# Measurement.net
KiCad netlist of a schematic drawn in Altium Designer
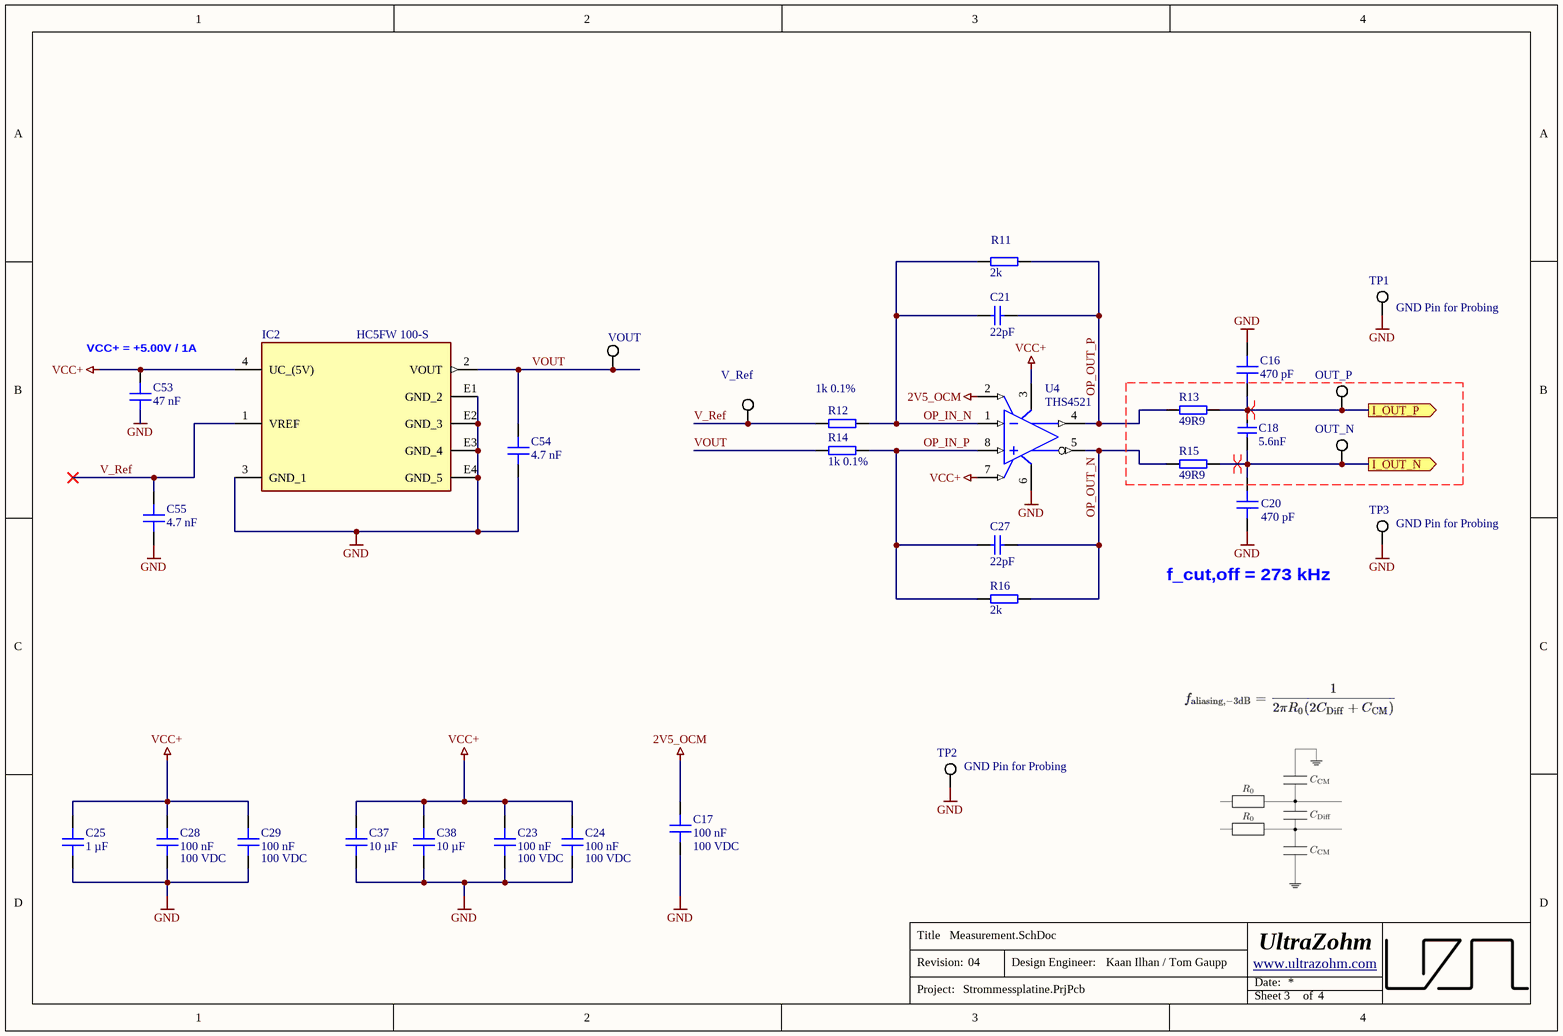
[diagram p0: Measurement.SchDoc]

(export (version "E")
  (design (tool "Eeschema 10.0.6"))
  (components
    (comp (ref "C16")
      (value "470 pF")
      (footprint "C_0603")
      (description "50V 470pF X7R ±10% 0603 Multilayer Ceramic Capacitors MLCC - SMD/SMT ROHS")
      (fields
        (field (name "MANUFACTURER PART NUMBER") "C0603C471K5RACAUTO")
        (field (name "MANUFACTURER") "KEMET")
        (field (name "CREATED FROM") "KIlhan")
      )
      (libsource (lib "user") (part "Capacitor"))
    )
    (comp (ref "C17")
      (value "100 nF")
      (footprint "C_0603")
      (description "100V 100nF X7S ±10% 0603 Multilayer Ceramic Capacitors MLCC - SMD/SMT ROHS")
      (fields
        (field (name "MANUFACTURER PART NUMBER") "C1608X7S2A104KT000N")
        (field (name "MANUFACTURER") "TDK")
        (field (name "VOLTAGE RATING") "100 VDC")
        (field (name "CREATED FROM") "AGeiger")
      )
      (libsource (lib "user") (part "Capacitor"))
    )
    (comp (ref "C18")
      (value "5.6nF")
      (footprint "C_0603_TE")
      (description "50V 5.6nF X7R ±10% 0603 Multilayer Ceramic Capacitors MLCC - SMD/SMT ROHS")
      (fields
        (field (name "MANUFACTURER PART NUMBER") "0603B562K500NT")
        (field (name "MANUFACTURER") "FH (Guangdong Fenghua Advanced Tech)")
        (field (name "CREATED FROM") "Kilhan")
      )
      (libsource (lib "user") (part "CAP-NP"))
    )
    (comp (ref "C20")
      (value "470 pF")
      (footprint "C_0603")
      (description "50V 470pF X7R ±10% 0603 Multilayer Ceramic Capacitors MLCC - SMD/SMT ROHS")
      (fields
        (field (name "MANUFACTURER PART NUMBER") "C0603C471K5RACAUTO")
        (field (name "MANUFACTURER") "KEMET")
        (field (name "CREATED FROM") "KIlhan")
      )
      (libsource (lib "user") (part "Capacitor"))
    )
    (comp (ref "C21")
      (value "22pF")
      (footprint "C_0603_TE")
      (description "50V 22pF C0G ±5% 0603 Multilayer Ceramic Capacitors MLCC - SMD/SMT ROHS")
      (fields
        (field (name "MANUFACTURER PART NUMBER") "CL10C220JB8NNNC")
        (field (name "MANUFACTURER") "Samsung Electro-Mechanics")
        (field (name "CREATED FROM") "Kilhan")
      )
      (libsource (lib "user") (part "CAP-NP"))
    )
    (comp (ref "C23")
      (value "100 nF")
      (footprint "C_0603")
      (description "100V 100nF X7S ±10% 0603 Multilayer Ceramic Capacitors MLCC - SMD/SMT ROHS")
      (fields
        (field (name "MANUFACTURER PART NUMBER") "C1608X7S2A104KT000N")
        (field (name "MANUFACTURER") "TDK")
        (field (name "VOLTAGE RATING") "100 VDC")
        (field (name "CREATED FROM") "AGeiger")
      )
      (libsource (lib "user") (part "Capacitor"))
    )
    (comp (ref "C24")
      (value "100 nF")
      (footprint "C_0603")
      (description "100V 100nF X7S ±10% 0603 Multilayer Ceramic Capacitors MLCC - SMD/SMT ROHS")
      (fields
        (field (name "MANUFACTURER PART NUMBER") "C1608X7S2A104KT000N")
        (field (name "MANUFACTURER") "TDK")
        (field (name "VOLTAGE RATING") "100 VDC")
        (field (name "CREATED FROM") "AGeiger")
      )
      (libsource (lib "user") (part "Capacitor"))
    )
    (comp (ref "C25")
      (value "1 µF")
      (footprint "C_0603")
      (description "50V 1uF X5R ±10% 0603  Multilayer Ceramic Capacitors MLCC - SMD/SMT ROHS")
      (fields
        (field (name "MANUFACTURER PART NUMBER") "CL10A105KB8NNNC")
        (field (name "MANUFACTURER") "Samsung Electro-Mechanics")
        (field (name "CREATED FROM") "MGremer")
      )
      (libsource (lib "user") (part "Capacitor"))
    )
    (comp (ref "C27")
      (value "22pF")
      (footprint "C_0603_TE")
      (description "50V 22pF C0G ±5% 0603 Multilayer Ceramic Capacitors MLCC - SMD/SMT ROHS")
      (fields
        (field (name "MANUFACTURER PART NUMBER") "CL10C220JB8NNNC")
        (field (name "MANUFACTURER") "Samsung Electro-Mechanics")
        (field (name "CREATED FROM") "Kilhan")
      )
      (libsource (lib "user") (part "CAP-NP"))
    )
    (comp (ref "C28")
      (value "100 nF")
      (footprint "C_0603")
      (description "100V 100nF X7S ±10% 0603 Multilayer Ceramic Capacitors MLCC - SMD/SMT ROHS")
      (fields
        (field (name "MANUFACTURER PART NUMBER") "C1608X7S2A104KT000N")
        (field (name "MANUFACTURER") "TDK")
        (field (name "VOLTAGE RATING") "100 VDC")
        (field (name "CREATED FROM") "AGeiger")
      )
      (libsource (lib "user") (part "Capacitor"))
    )
    (comp (ref "C29")
      (value "100 nF")
      (footprint "C_0603")
      (description "100V 100nF X7S ±10% 0603 Multilayer Ceramic Capacitors MLCC - SMD/SMT ROHS")
      (fields
        (field (name "MANUFACTURER PART NUMBER") "C1608X7S2A104KT000N")
        (field (name "MANUFACTURER") "TDK")
        (field (name "VOLTAGE RATING") "100 VDC")
        (field (name "CREATED FROM") "AGeiger")
      )
      (libsource (lib "user") (part "Capacitor"))
    )
    (comp (ref "C37")
      (value "10 µF")
      (footprint "C0805")
      (description "Capacitor 0805, 35 VDC, 10 µF, X5R")
      (fields
        (field (name "MANUFACTURER PART NUMBER") "GRM21BR6YA106KE43L")
        (field (name "MANUFACTURER") "muRata")
        (field (name "CREATED FROM") "MGremer")
      )
      (libsource (lib "user") (part "Capacitor"))
    )
    (comp (ref "C38")
      (value "10 µF")
      (footprint "C0805")
      (description "Capacitor 0805, 35 VDC, 10 µF, X5R")
      (fields
        (field (name "MANUFACTURER PART NUMBER") "GRM21BR6YA106KE43L")
        (field (name "MANUFACTURER") "muRata")
        (field (name "CREATED FROM") "MGremer")
      )
      (libsource (lib "user") (part "Capacitor"))
    )
    (comp (ref "C53")
      (value "47 nF")
      (footprint "C_0603")
      (description "Capacitor 0603, 50 VDC, 47 nF, X7R")
      (fields
        (field (name "MANUFACTURER PART NUMBER") "CL10B473KB8NNNC")
        (field (name "MANUFACTURER") "Samsung Electro-Mechanics")
        (field (name "CREATED FROM") "DHufnagel")
      )
      (libsource (lib "user") (part "Capacitor"))
    )
    (comp (ref "C54")
      (value "4.7 nF")
      (footprint "C_0603")
      (description "Capacitor 0603, 16 VDC, 4.7 nF, X7R")
      (fields
        (field (name "MANUFACTURER PART NUMBER") "C0603C472K4RECAUTO")
        (field (name "MANUFACTURER") "KEMET")
        (field (name "CREATED FROM") "MGremer")
      )
      (libsource (lib "user") (part "Capacitor"))
    )
    (comp (ref "C55")
      (value "4.7 nF")
      (footprint "C_0603")
      (description "Capacitor 0603, 16 VDC, 4.7 nF, X7R")
      (fields
        (field (name "MANUFACTURER PART NUMBER") "C0603C472K4RECAUTO")
        (field (name "MANUFACTURER") "KEMET")
        (field (name "CREATED FROM") "MGremer")
      )
      (libsource (lib "user") (part "Capacitor"))
    )
    (comp (ref "IC2")
      (value "HC5FW 100-S")
      (footprint "LEM_HC5FW")
      (description "-100 A - 100 A, 40 kHz")
      (fields (field (name "MANUFACTURER") "LEM") (field (name "CREATED FROM") "TGaupp"))
      (libsource (lib "user") (part "LEM_HC5FW"))
    )
    (comp (ref "OUT_N")
      (value "5015")
      (footprint "KSTN-5019_V")
      (description "Circuit Board Hardware - PCB SM TEST POINT ON T&R - MINIATURE")
      (fields
        (field (name "MANUFACTURER") "Keystone Electronics")
        (field (name "LCSC PART NUMBER") "C5199798")
        (field (name "CREATED FROM") "AGeiger")
      )
      (libsource (lib "user") (part "SMD Testpoint"))
    )
    (comp (ref "OUT_P")
      (value "5015")
      (footprint "KSTN-5019_V")
      (description "Circuit Board Hardware - PCB SM TEST POINT ON T&R - MINIATURE")
      (fields
        (field (name "MANUFACTURER") "Keystone Electronics")
        (field (name "LCSC PART NUMBER") "C5199798")
        (field (name "CREATED FROM") "AGeiger")
      )
      (libsource (lib "user") (part "SMD Testpoint"))
    )
    (comp (ref "R11")
      (value "2k")
      (footprint "RES 0603_1608")
      (description "SMD resistor 0.1%")
      (fields
        (field (name "MANUFACTURER PART NUMBER") "ERJ-PB3B2001V")
        (field (name "MANUFACTURER") "Panasonic")
        (field (name "CREATED FROM") "DHufnagel")
      )
      (libsource (lib "user") (part "Resistor"))
    )
    (comp (ref "R12")
      (value "1k 0.1%")
      (footprint "RES 0603_1608")
      (description "100mW ±0.1% ±25ppm/℃ 1kΩ 0603 Chip Resistor - Surface Mount ROHS")
      (fields
        (field (name "MANUFACTURER PART NUMBER") "AR03BTCX1001")
        (field (name "MANUFACTURER") "Viking Tech")
        (field (name "CREATED FROM") "AGeiger")
      )
      (libsource (lib "user") (part "Resistor"))
    )
    (comp (ref "R13")
      (value "49R9")
      (footprint "RES 0603_1608")
      (description "100mW Thick Film Resistors ±100ppm/℃ ±1% 49.9Ω 0603 Chip Resistor - Surface Mount ROHS")
      (fields
        (field (name "MANUFACTURER PART NUMBER") "RC0603FR-0749R9L")
        (field (name "MANUFACTURER") "YAGEO")
        (field (name "CREATED FROM") "AGeiger")
      )
      (libsource (lib "user") (part "Resistor"))
    )
    (comp (ref "R14")
      (value "1k 0.1%")
      (footprint "RES 0603_1608")
      (description "100mW ±0.1% ±25ppm/℃ 1kΩ 0603 Chip Resistor - Surface Mount ROHS")
      (fields
        (field (name "MANUFACTURER PART NUMBER") "AR03BTCX1001")
        (field (name "MANUFACTURER") "Viking Tech")
        (field (name "CREATED FROM") "AGeiger")
      )
      (libsource (lib "user") (part "Resistor"))
    )
    (comp (ref "R15")
      (value "49R9")
      (footprint "RES 0603_1608")
      (description "100mW Thick Film Resistors ±100ppm/℃ ±1% 49.9Ω 0603 Chip Resistor - Surface Mount ROHS")
      (fields
        (field (name "MANUFACTURER PART NUMBER") "RC0603FR-0749R9L")
        (field (name "MANUFACTURER") "YAGEO")
        (field (name "CREATED FROM") "AGeiger")
      )
      (libsource (lib "user") (part "Resistor"))
    )
    (comp (ref "R16")
      (value "2k")
      (footprint "RES 0603_1608")
      (description "SMD resistor 0.1%")
      (fields
        (field (name "MANUFACTURER PART NUMBER") "ERJ-PB3B2001V")
        (field (name "MANUFACTURER") "Panasonic")
        (field (name "CREATED FROM") "DHufnagel")
      )
      (libsource (lib "user") (part "Resistor"))
    )
    (comp (ref "TP1")
      (value "5015")
      (footprint "KSTN-5019_V")
      (description "Circuit Board Hardware - PCB SM TEST POINT ON T&R - MINIATURE")
      (fields
        (field (name "MANUFACTURER") "Keystone Electronics")
        (field (name "LCSC PART NUMBER") "C5199798")
        (field (name "CREATED FROM") "AGeiger")
      )
      (libsource (lib "user") (part "SMD Testpoint"))
    )
    (comp (ref "TP2")
      (value "5015")
      (footprint "KSTN-5019_V")
      (description "Circuit Board Hardware - PCB SM TEST POINT ON T&R - MINIATURE")
      (fields
        (field (name "MANUFACTURER") "Keystone Electronics")
        (field (name "LCSC PART NUMBER") "C5199798")
        (field (name "CREATED FROM") "AGeiger")
      )
      (libsource (lib "user") (part "SMD Testpoint"))
    )
    (comp (ref "TP3")
      (value "5015")
      (footprint "KSTN-5019_V")
      (description "Circuit Board Hardware - PCB SM TEST POINT ON T&R - MINIATURE")
      (fields
        (field (name "MANUFACTURER") "Keystone Electronics")
        (field (name "LCSC PART NUMBER") "C5199798")
        (field (name "CREATED FROM") "AGeiger")
      )
      (libsource (lib "user") (part "SMD Testpoint"))
    )
    (comp (ref "U4")
      (value "THS4521")
      (footprint "ADA4940-1ARZ-R7")
      (description "145MHz 240uV 700nA Single Channel 95MHz SOIC-8 Differential Amplifiers ROHS")
      (fields
        (field (name "MANUFACTURER") "Texas Instruments")
        (field (name "MANUFACTURER PART NUMBER") "THS4521IDR")
      )
      (libsource (lib "UltraZohm_ADC") (part "THS4521IDGKR"))
    )
    (comp (ref "VOUT")
      (value "5019")
      (footprint "KSTN-5019_V")
      (description "Circuit Board Hardware - PCB SM TEST POINT ON T&R - MINIATURE")
      (fields
        (field (name "MANUFACTURER") "Keystone Electronics")
        (field (name "LCSC PART NUMBER") "C5199800")
        (field (name "CREATED FROM") "AGeiger")
      )
      (libsource (lib "user") (part "SMD Testpoint"))
    )
    (comp (ref "V_Ref")
      (value "5015")
      (footprint "KSTN-5019_V")
      (description "Circuit Board Hardware - PCB SM TEST POINT ON T&R - MINIATURE")
      (fields
        (field (name "MANUFACTURER") "Keystone Electronics")
        (field (name "LCSC PART NUMBER") "C5199798")
        (field (name "CREATED FROM") "AGeiger")
      )
      (libsource (lib "user") (part "SMD Testpoint"))
    )
  )
  (nets
    (net (code "1") (name "/I_OUT_N") (class "Default")
      (node (ref "C18") (pin "2") (pinfunction "2_2") (pintype "passive"))
      (node (ref "C20") (pin "1") (pinfunction "1_1") (pintype "passive"))
      (node (ref "OUT_N") (pin "1") (pinfunction "1_1") (pintype "passive"))
      (node (ref "R15") (pin "2") (pinfunction "2_2") (pintype "passive"))
    )
    (net (code "2") (name "/I_OUT_P") (class "Default")
      (node (ref "C16") (pin "2") (pinfunction "2_2") (pintype "passive"))
      (node (ref "C18") (pin "1") (pinfunction "1_1") (pintype "passive"))
      (node (ref "OUT_P") (pin "1") (pinfunction "1_1") (pintype "passive"))
      (node (ref "R13") (pin "2") (pinfunction "2_2") (pintype "passive"))
    )
    (net (code "3") (name "/OP_IN_N") (class "Default")
      (node (ref "C21") (pin "2") (pinfunction "2_2") (pintype "passive"))
      (node (ref "R11") (pin "1") (pinfunction "1_1") (pintype "passive"))
      (node (ref "R12") (pin "2") (pinfunction "2_2") (pintype "passive"))
      (node (ref "U4") (pin "1") (pinfunction "VIN-_1") (pintype "input"))
    )
    (net (code "4") (name "/OP_IN_P") (class "Default")
      (node (ref "C27") (pin "2") (pinfunction "2_2") (pintype "passive"))
      (node (ref "R14") (pin "2") (pinfunction "2_2") (pintype "passive"))
      (node (ref "R16") (pin "1") (pinfunction "1_1") (pintype "passive"))
      (node (ref "U4") (pin "8") (pinfunction "VIN+_8") (pintype "input"))
    )
    (net (code "5") (name "/OP_OUT_N") (class "Default")
      (node (ref "C27") (pin "1") (pinfunction "1_1") (pintype "passive"))
      (node (ref "R15") (pin "1") (pinfunction "1_1") (pintype "passive"))
      (node (ref "R16") (pin "2") (pinfunction "2_2") (pintype "passive"))
      (node (ref "U4") (pin "5") (pinfunction "VOUT-_5") (pintype "output"))
    )
    (net (code "6") (name "/OP_OUT_P") (class "Default")
      (node (ref "C21") (pin "1") (pinfunction "1_1") (pintype "passive"))
      (node (ref "R11") (pin "2") (pinfunction "2_2") (pintype "passive"))
      (node (ref "R13") (pin "1") (pinfunction "1_1") (pintype "passive"))
      (node (ref "U4") (pin "4") (pinfunction "VOUT+_4") (pintype "output"))
    )
    (net (code "7") (name "/VOUT") (class "Default")
      (node (ref "C54") (pin "2") (pinfunction "2_2") (pintype "passive"))
      (node (ref "IC2") (pin "2") (pinfunction "VOUT_2") (pintype "output"))
      (node (ref "R14") (pin "1") (pinfunction "1_1") (pintype "passive"))
      (node (ref "VOUT") (pin "1") (pinfunction "1_1") (pintype "passive"))
    )
    (net (code "8") (name "/V_Ref") (class "Default")
      (node (ref "C55") (pin "2") (pinfunction "2_2") (pintype "passive"))
      (node (ref "IC2") (pin "1") (pinfunction "VREF_1") (pintype "passive"))
      (node (ref "R12") (pin "1") (pinfunction "1_1") (pintype "passive"))
      (node (ref "V_Ref") (pin "1") (pinfunction "1_1") (pintype "passive"))
    )
    (net (code "9") (name "2V5_OCM") (class "Default")
      (node (ref "C17") (pin "1") (pinfunction "1_1") (pintype "passive"))
      (node (ref "U4") (pin "2") (pinfunction "VOCM_2") (pintype "input"))
    )
    (net (code "10") (name "GND") (class "Default")
      (node (ref "C16") (pin "1") (pinfunction "1_1") (pintype "passive"))
      (node (ref "C17") (pin "2") (pinfunction "2_2") (pintype "passive"))
      (node (ref "C20") (pin "2") (pinfunction "2_2") (pintype "passive"))
      (node (ref "C23") (pin "1") (pinfunction "1_1") (pintype "passive"))
      (node (ref "C24") (pin "1") (pinfunction "1_1") (pintype "passive"))
      (node (ref "C25") (pin "1") (pinfunction "1_1") (pintype "passive"))
      (node (ref "C28") (pin "1") (pinfunction "1_1") (pintype "passive"))
      (node (ref "C29") (pin "1") (pinfunction "1_1") (pintype "passive"))
      (node (ref "C37") (pin "1") (pinfunction "1_1") (pintype "passive"))
      (node (ref "C38") (pin "1") (pinfunction "1_1") (pintype "passive"))
      (node (ref "C53") (pin "1") (pinfunction "1_1") (pintype "passive"))
      (node (ref "C54") (pin "1") (pinfunction "1_1") (pintype "passive"))
      (node (ref "C55") (pin "1") (pinfunction "1_1") (pintype "passive"))
      (node (ref "IC2") (pin "3") (pinfunction "GND_1_3") (pintype "passive"))
      (node (ref "IC2") (pin "E1") (pinfunction "GND_2_E1") (pintype "passive"))
      (node (ref "IC2") (pin "E2") (pinfunction "GND_3_E2") (pintype "passive"))
      (node (ref "IC2") (pin "E3") (pinfunction "GND_4_E3") (pintype "passive"))
      (node (ref "IC2") (pin "E4") (pinfunction "GND_5_E4") (pintype "passive"))
      (node (ref "TP1") (pin "1") (pinfunction "1_1") (pintype "passive"))
      (node (ref "TP2") (pin "1") (pinfunction "1_1") (pintype "passive"))
      (node (ref "TP3") (pin "1") (pinfunction "1_1") (pintype "passive"))
      (node (ref "U4") (pin "6") (pinfunction "VS-_6") (pintype "power_in"))
    )
    (net (code "11") (name "VCC+") (class "Default")
      (node (ref "C23") (pin "2") (pinfunction "2_2") (pintype "passive"))
      (node (ref "C24") (pin "2") (pinfunction "2_2") (pintype "passive"))
      (node (ref "C25") (pin "2") (pinfunction "2_2") (pintype "passive"))
      (node (ref "C28") (pin "2") (pinfunction "2_2") (pintype "passive"))
      (node (ref "C29") (pin "2") (pinfunction "2_2") (pintype "passive"))
      (node (ref "C37") (pin "2") (pinfunction "2_2") (pintype "passive"))
      (node (ref "C38") (pin "2") (pinfunction "2_2") (pintype "passive"))
      (node (ref "C53") (pin "2") (pinfunction "2_2") (pintype "passive"))
      (node (ref "IC2") (pin "4") (pinfunction "UC_(5V)_4") (pintype "passive"))
      (node (ref "U4") (pin "3") (pinfunction "VS+_3") (pintype "power_in"))
      (node (ref "U4") (pin "7") (pinfunction "~{PD}_7") (pintype "input"))
    )
  )
)
